# Smart-LCD_1V1.net
KiCad netlist of a schematic drawn in EAGLE
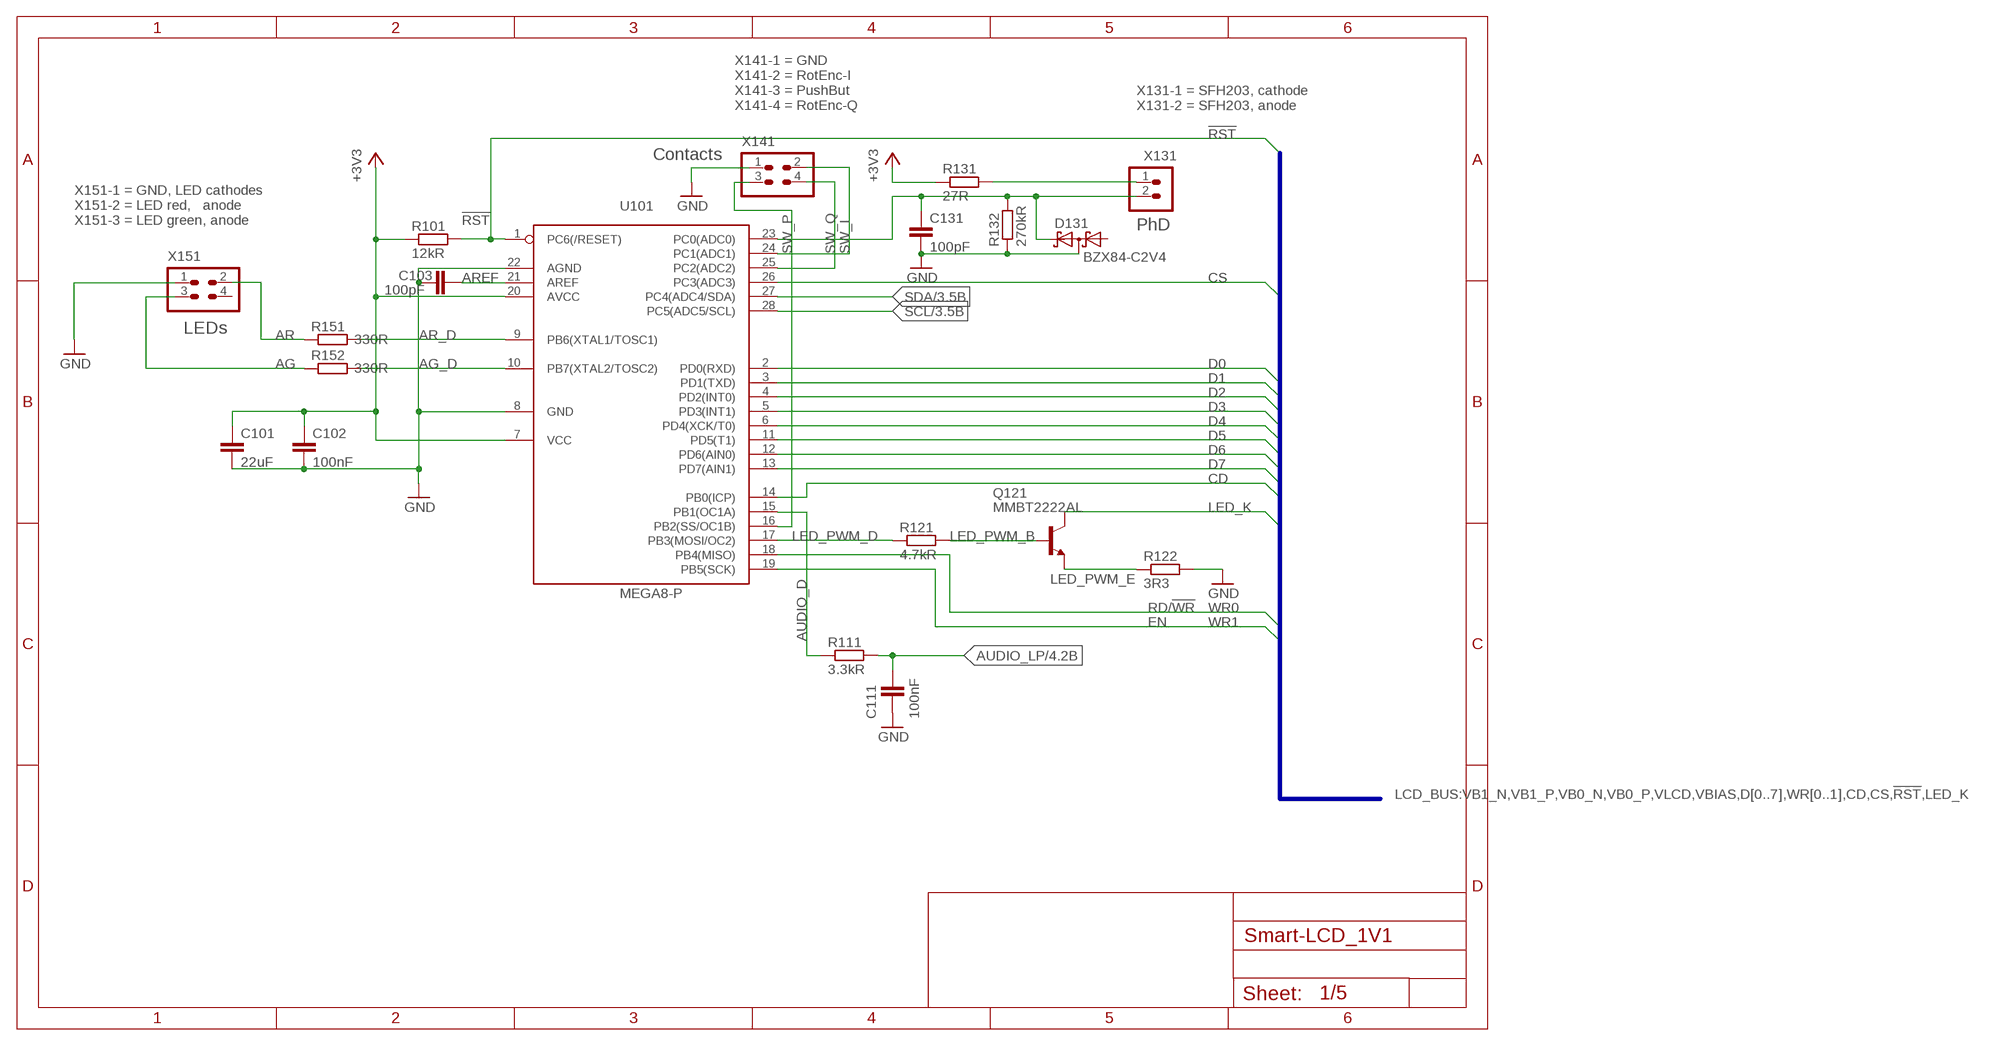
[diagram p0: schematic, sheet 1]
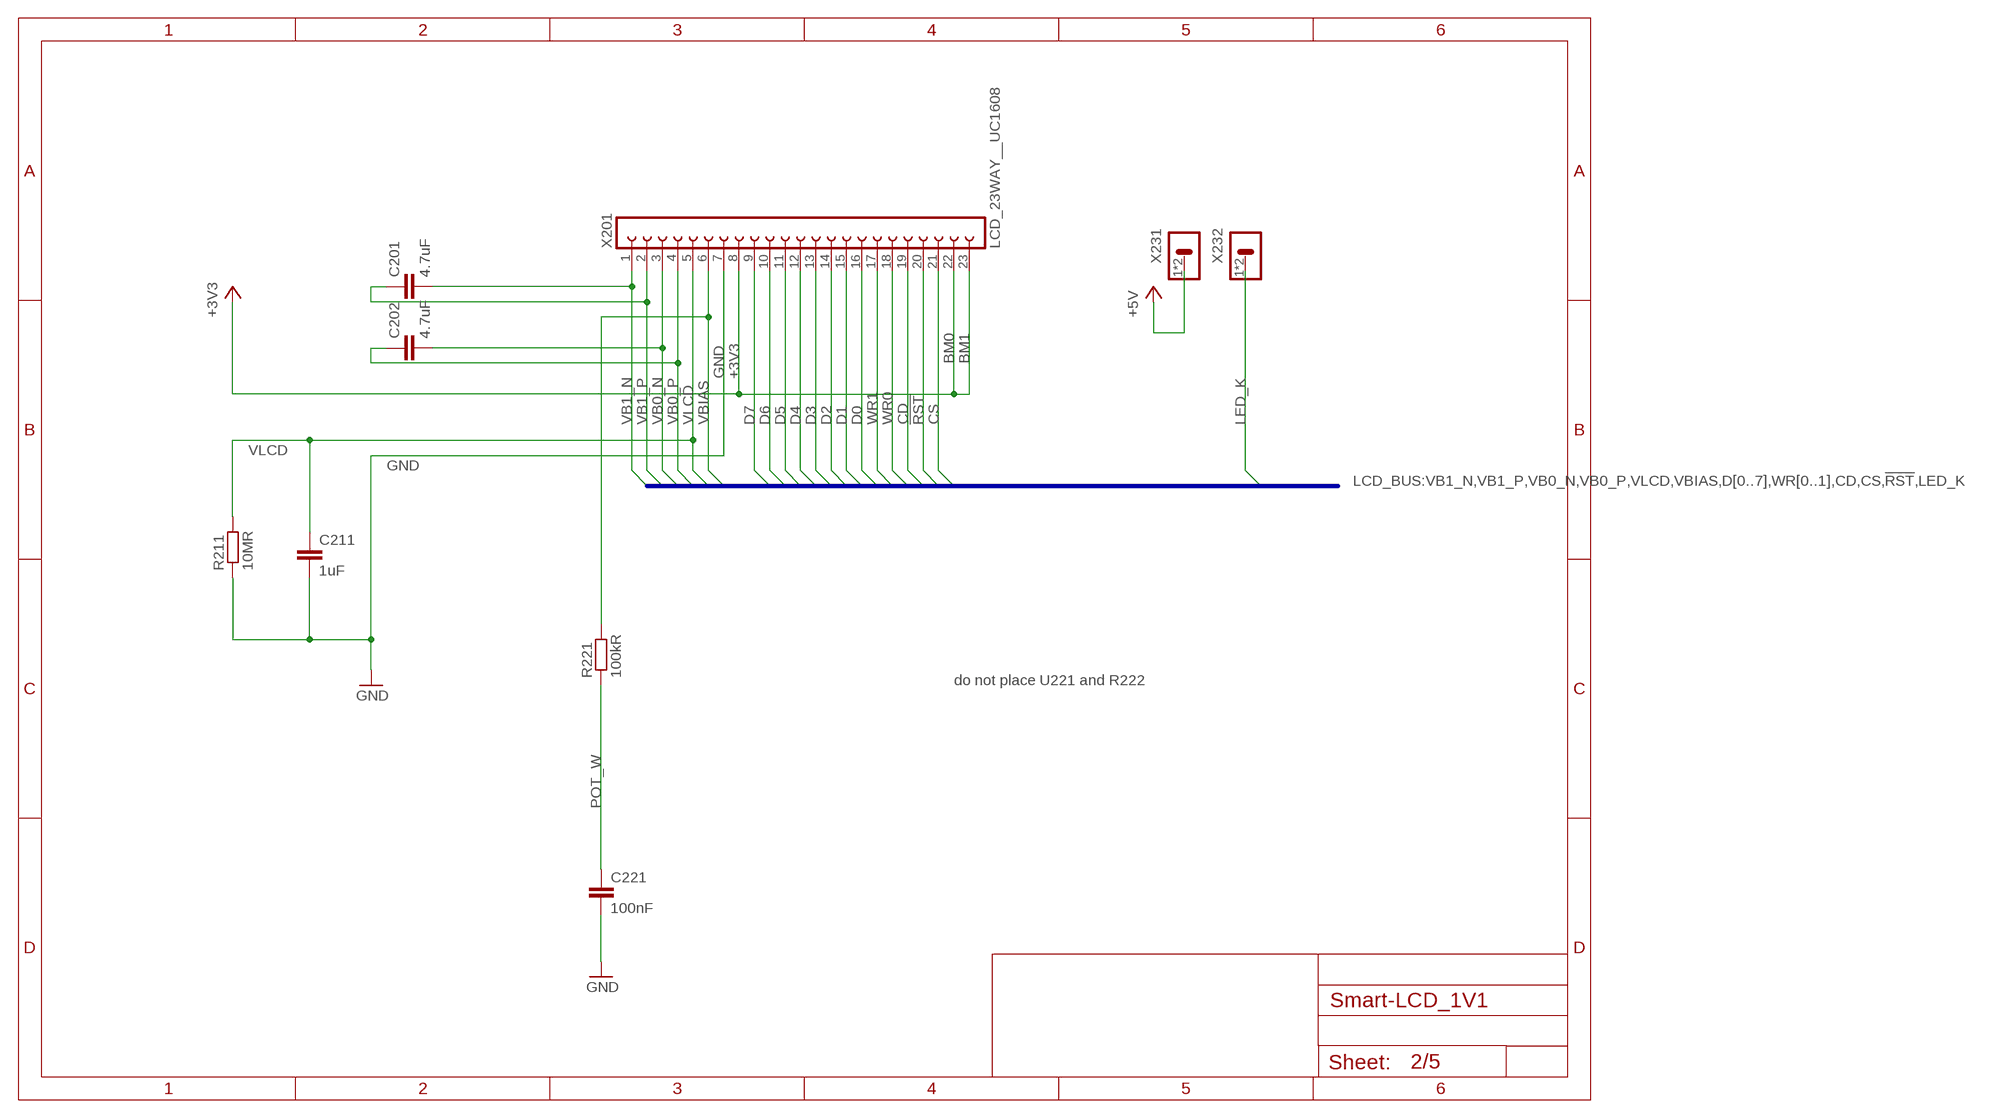
[diagram p1: schematic, sheet 2]
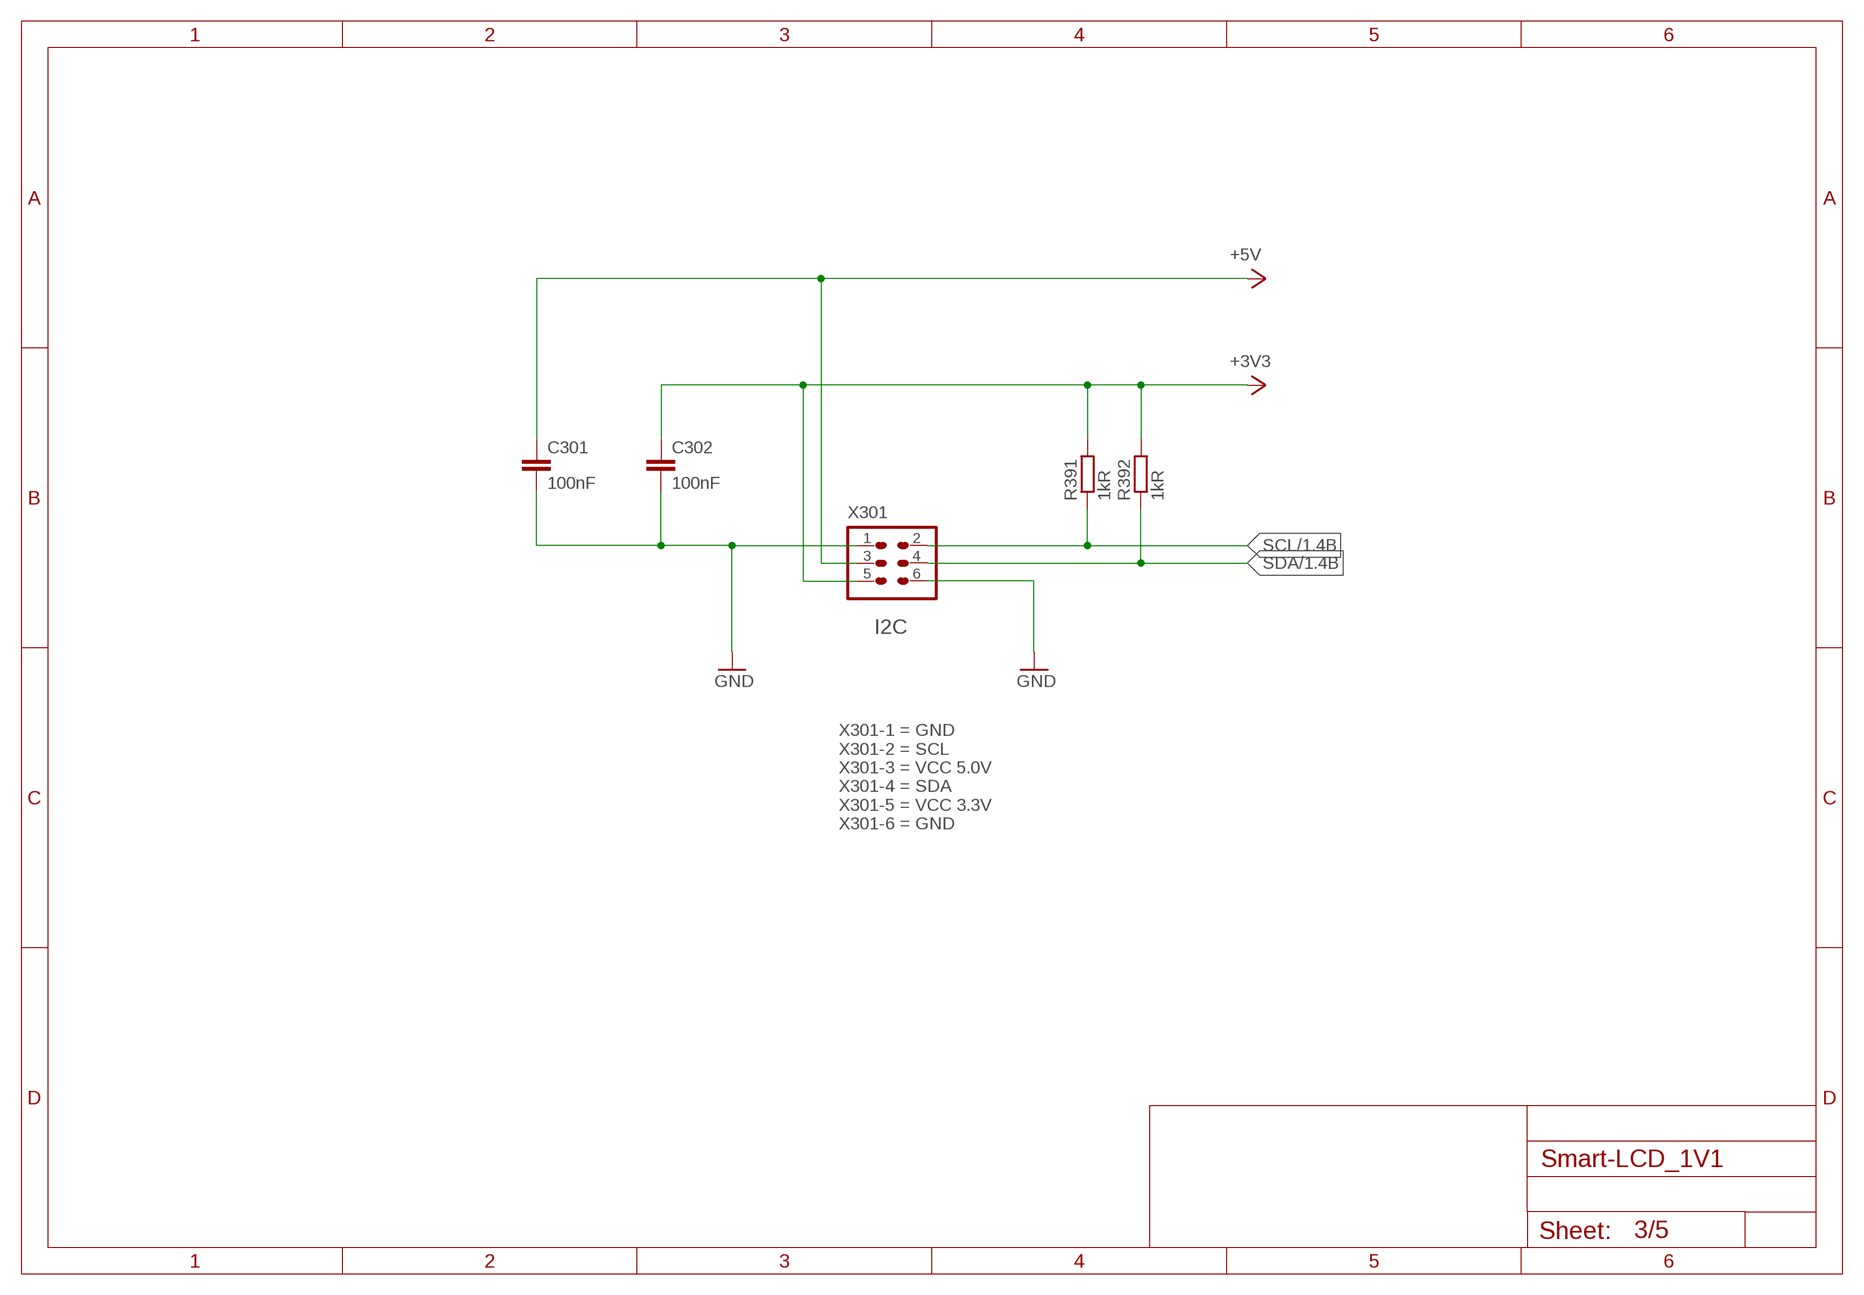
[diagram p2: schematic, sheet 3]
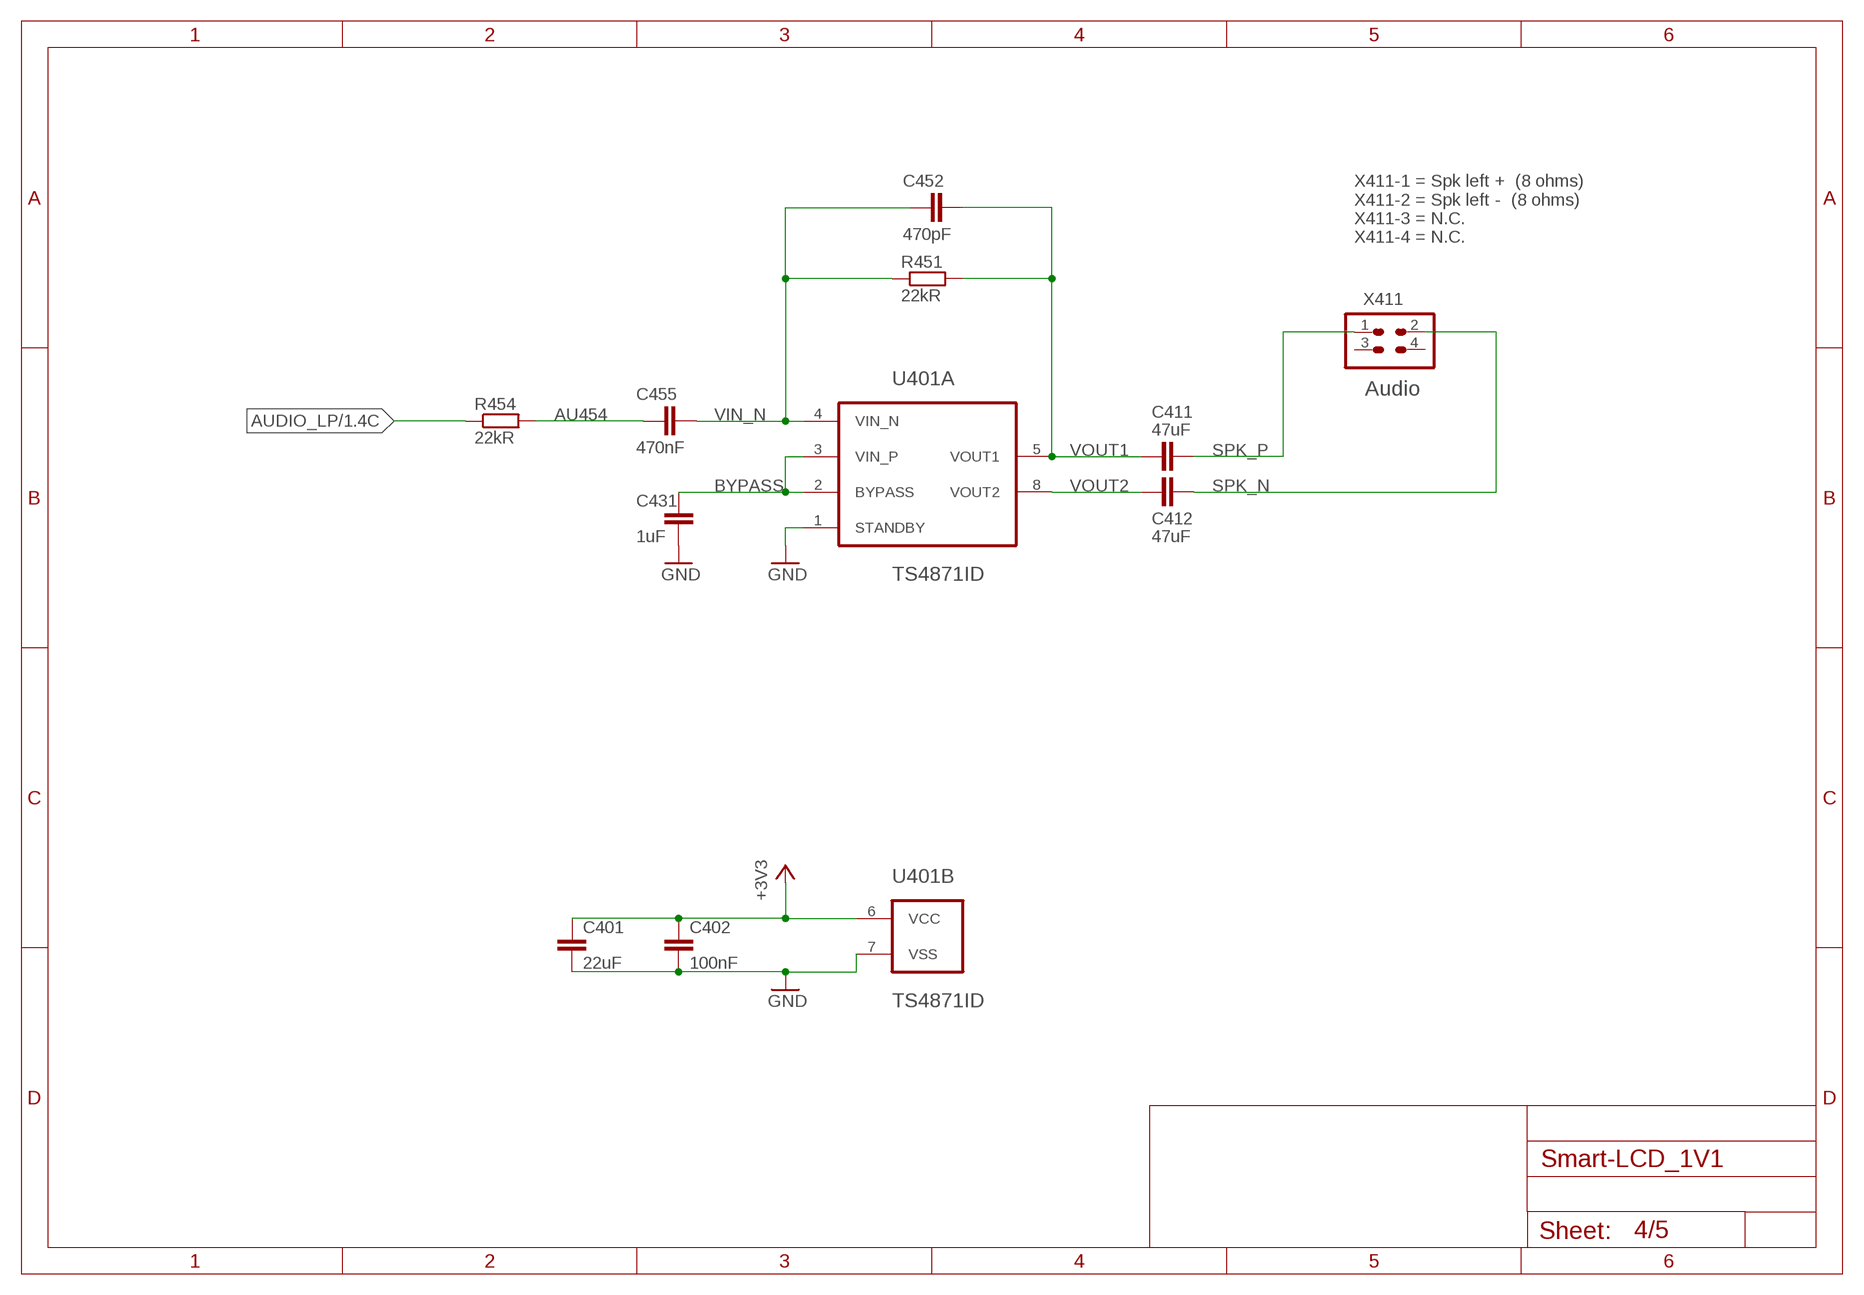
[diagram p3: schematic, sheet 4]
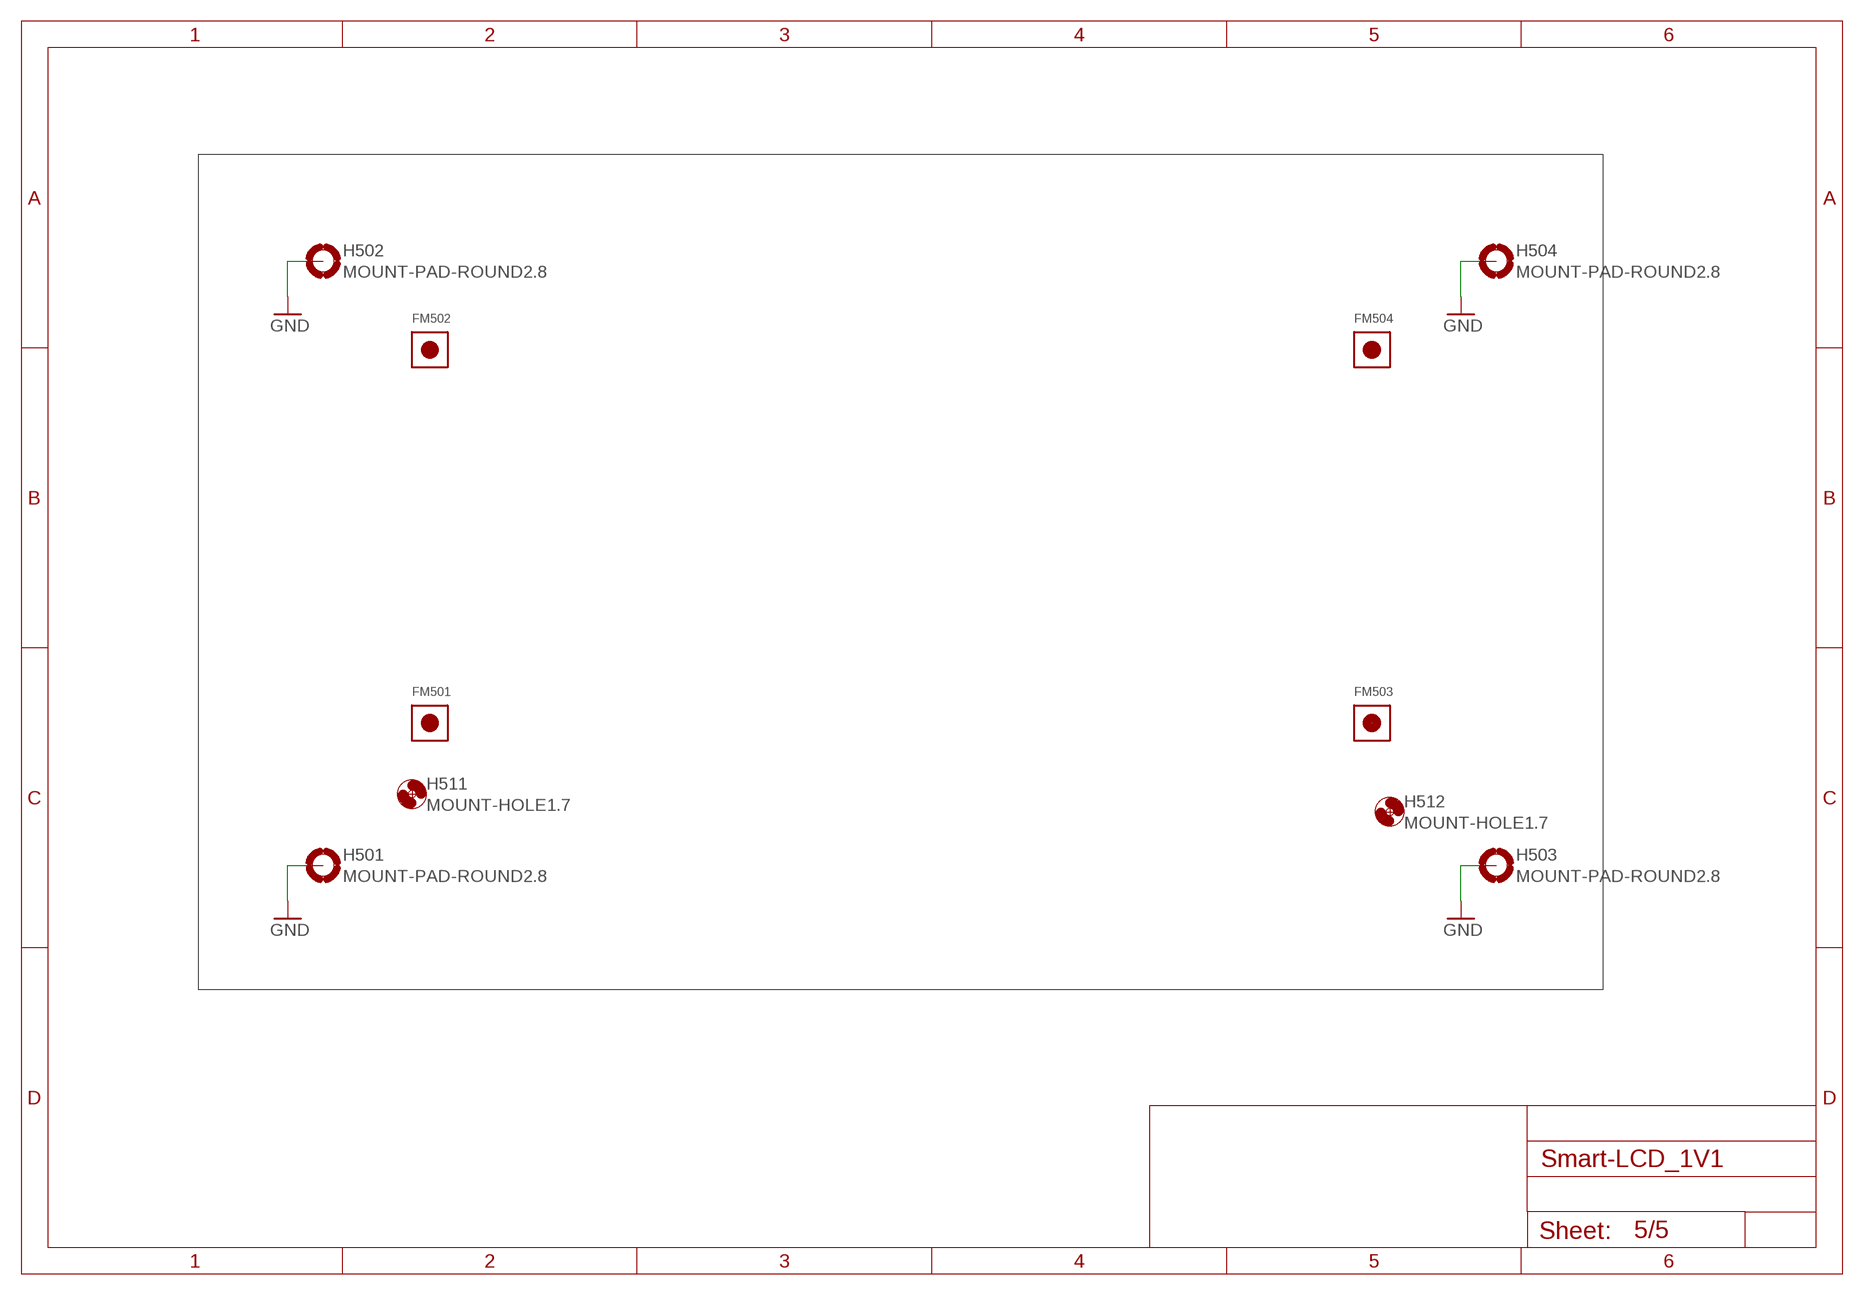
[diagram p4: schematic, sheet 5]

(export (version "E")
  (design (tool "Eeschema 10.0.6"))
  (components
    (comp (ref "C201")
      (value "4.7uF")
      (footprint "eagle-import:C0805")
      (libsource (lib "eagle-import") (part "C-EUC0805"))
    )
    (comp (ref "C202")
      (value "4.7uF")
      (footprint "eagle-import:C0805")
      (libsource (lib "eagle-import") (part "C-EUC0805"))
    )
    (comp (ref "C211")
      (value "1uF")
      (footprint "eagle-import:C0805")
      (libsource (lib "eagle-import") (part "C-EUC0805"))
    )
    (comp (ref "C221")
      (value "100nF")
      (footprint "eagle-import:C0805")
      (libsource (lib "eagle-import") (part "C-EUC0805"))
    )
    (comp (ref "R211")
      (value "10MR")
      (footprint "eagle-import:R0805")
      (libsource (lib "eagle-import") (part "R-EU_R0805"))
    )
    (comp (ref "R221")
      (value "100kR")
      (footprint "eagle-import:R0805")
      (libsource (lib "eagle-import") (part "R-EU_R0805"))
    )
    (comp (ref "X201")
      (value "LCD_23WAY__UC1608")
      (footprint "eagle-import:23X01_1MM27__UC1608")
      (libsource (lib "eagle-import") (part "LCD_23WAY__UC1608"))
    )
    (comp (ref "X231")
      (value "LED_A")
      (footprint "eagle-import:P1-20X0.80")
      (libsource (lib "eagle-import") (part "CON_1X"))
    )
    (comp (ref "X232")
      (value "LED_K")
      (footprint "eagle-import:P1-20X0.80")
      (libsource (lib "eagle-import") (part "CON_1X"))
    )
    (comp (ref "C101")
      (value "22uF")
      (footprint "eagle-import:C0805")
      (libsource (lib "eagle-import") (part "C-EUC0805"))
    )
    (comp (ref "C102")
      (value "100nF")
      (footprint "eagle-import:C0805")
      (libsource (lib "eagle-import") (part "C-EUC0805"))
    )
    (comp (ref "C103")
      (value "100pF")
      (footprint "eagle-import:C0805")
      (libsource (lib "eagle-import") (part "C-EUC0805"))
    )
    (comp (ref "C111")
      (value "100nF")
      (footprint "eagle-import:C0805")
      (libsource (lib "eagle-import") (part "C-EUC0805"))
    )
    (comp (ref "C131")
      (value "100pF")
      (footprint "eagle-import:C0805")
      (libsource (lib "eagle-import") (part "C-EUC0805"))
    )
    (comp (ref "D131")
      (value "BZX84-C2V4")
      (footprint "eagle-import:SOT23")
      (libsource (lib "eagle-import") (part "BAS70-04"))
    )
    (comp (ref "Q121")
      (value "MMBT2222AL")
      (footprint "eagle-import:SOT23")
      (libsource (lib "eagle-import") (part "MMBT2222AL"))
    )
    (comp (ref "R101")
      (value "12kR")
      (footprint "eagle-import:R0805")
      (libsource (lib "eagle-import") (part "R-EU_R0805"))
    )
    (comp (ref "R111")
      (value "3.3kR")
      (footprint "eagle-import:R0805")
      (libsource (lib "eagle-import") (part "R-EU_R0805"))
    )
    (comp (ref "R121")
      (value "4.7kR")
      (footprint "eagle-import:R0805")
      (libsource (lib "eagle-import") (part "R-EU_R0805"))
    )
    (comp (ref "R122")
      (value "3R3")
      (footprint "eagle-import:R0805")
      (libsource (lib "eagle-import") (part "R-EU_R0805"))
    )
    (comp (ref "R131")
      (value "27R")
      (footprint "eagle-import:R0805")
      (libsource (lib "eagle-import") (part "R-EU_R0805"))
    )
    (comp (ref "R132")
      (value "270kR")
      (footprint "eagle-import:R0805")
      (libsource (lib "eagle-import") (part "R-EU_R0805"))
    )
    (comp (ref "R151")
      (value "330R")
      (footprint "eagle-import:R0805")
      (libsource (lib "eagle-import") (part "R-EU_R0805"))
    )
    (comp (ref "R152")
      (value "330R")
      (footprint "eagle-import:R0805")
      (libsource (lib "eagle-import") (part "R-EU_R0805"))
    )
    (comp (ref "U101")
      (value "MEGA8-P")
      (footprint "eagle-import:DIL28-3")
      (libsource (lib "eagle-import") (part "MEGA8-P"))
    )
    (comp (ref "X131")
      (value "LDR")
      (footprint "eagle-import:1X02")
      (libsource (lib "eagle-import") (part "HEADER-1X2"))
    )
    (comp (ref "X141")
      (value "Switches")
      (footprint "eagle-import:2X02")
      (libsource (lib "eagle-import") (part "HEADER-2X2"))
    )
    (comp (ref "X151")
      (value "LEDs")
      (footprint "eagle-import:2X02")
      (libsource (lib "eagle-import") (part "HEADER-2X2"))
    )
    (comp (ref "FM501")
      (value "FIDUCIAL_MARK_1MM")
      (footprint "eagle-import:FIDUCIAL_MARK_1MM")
      (libsource (lib "eagle-import") (part "FIDUCIAL_MARK_1MM"))
    )
    (comp (ref "FM502")
      (value "FIDUCIAL_MARK_1MM")
      (footprint "eagle-import:FIDUCIAL_MARK_1MM")
      (libsource (lib "eagle-import") (part "FIDUCIAL_MARK_1MM"))
    )
    (comp (ref "FM503")
      (value "FIDUCIAL_MARK_1MM")
      (footprint "eagle-import:FIDUCIAL_MARK_1MM")
      (libsource (lib "eagle-import") (part "FIDUCIAL_MARK_1MM"))
    )
    (comp (ref "FM504")
      (value "FIDUCIAL_MARK_1MM")
      (footprint "eagle-import:FIDUCIAL_MARK_1MM")
      (libsource (lib "eagle-import") (part "FIDUCIAL_MARK_1MM"))
    )
    (comp (ref "H501")
      (value "MOUNT-PAD-ROUND2.8")
      (footprint "eagle-import:2,8-PAD")
      (libsource (lib "eagle-import") (part "MOUNT-PAD-ROUND2.8"))
    )
    (comp (ref "H502")
      (value "MOUNT-PAD-ROUND2.8")
      (footprint "eagle-import:2,8-PAD")
      (libsource (lib "eagle-import") (part "MOUNT-PAD-ROUND2.8"))
    )
    (comp (ref "H503")
      (value "MOUNT-PAD-ROUND2.8")
      (footprint "eagle-import:2,8-PAD")
      (libsource (lib "eagle-import") (part "MOUNT-PAD-ROUND2.8"))
    )
    (comp (ref "H504")
      (value "MOUNT-PAD-ROUND2.8")
      (footprint "eagle-import:2,8-PAD")
      (libsource (lib "eagle-import") (part "MOUNT-PAD-ROUND2.8"))
    )
    (comp (ref "H511")
      (value "MOUNT-HOLE1.7")
      (footprint "eagle-import:1,7")
      (libsource (lib "eagle-import") (part "MOUNT-HOLE1.7"))
    )
    (comp (ref "H512")
      (value "MOUNT-HOLE1.7")
      (footprint "eagle-import:1,7")
      (libsource (lib "eagle-import") (part "MOUNT-HOLE1.7"))
    )
    (comp (ref "C301")
      (value "100nF")
      (footprint "eagle-import:C0805")
      (libsource (lib "eagle-import") (part "C-EUC0805"))
    )
    (comp (ref "C302")
      (value "100nF")
      (footprint "eagle-import:C0805")
      (libsource (lib "eagle-import") (part "C-EUC0805"))
    )
    (comp (ref "R391")
      (value "1kR")
      (footprint "eagle-import:R0805")
      (libsource (lib "eagle-import") (part "R-EU_R0805"))
    )
    (comp (ref "R392")
      (value "1kR")
      (footprint "eagle-import:R0805")
      (libsource (lib "eagle-import") (part "R-EU_R0805"))
    )
    (comp (ref "X301")
      (value "I2C")
      (footprint "eagle-import:2X03")
      (libsource (lib "eagle-import") (part "HEADER-2X3"))
    )
    (comp (ref "C401")
      (value "22uF")
      (footprint "eagle-import:C0805")
      (libsource (lib "eagle-import") (part "C-EUC0805"))
    )
    (comp (ref "C402")
      (value "100nF")
      (footprint "eagle-import:C0805")
      (libsource (lib "eagle-import") (part "C-EUC0805"))
    )
    (comp (ref "C411")
      (value "47uF")
      (footprint "eagle-import:C0805")
      (libsource (lib "eagle-import") (part "C-EUC0805"))
    )
    (comp (ref "C412")
      (value "47uF")
      (footprint "eagle-import:C0805")
      (libsource (lib "eagle-import") (part "C-EUC0805"))
    )
    (comp (ref "C431")
      (value "1uF")
      (footprint "eagle-import:C0805")
      (libsource (lib "eagle-import") (part "C-EUC0805"))
    )
    (comp (ref "C452")
      (value "470pF")
      (footprint "eagle-import:C0805")
      (libsource (lib "eagle-import") (part "C-EUC0805"))
    )
    (comp (ref "C455")
      (value "470nF")
      (footprint "eagle-import:C0805")
      (libsource (lib "eagle-import") (part "C-EUC0805"))
    )
    (comp (ref "R451")
      (value "22kR")
      (footprint "eagle-import:R0805")
      (libsource (lib "eagle-import") (part "R-EU_R0805"))
    )
    (comp (ref "R454")
      (value "22kR")
      (footprint "eagle-import:R0805")
      (libsource (lib "eagle-import") (part "R-EU_R0805"))
    )
    (comp (ref "U401")
      (value "TS4871ID")
      (footprint "eagle-import:SO08")
      (libsource (lib "eagle-import") (part "TS4871ID"))
    )
    (comp (ref "X411")
      (value "Audio")
      (footprint "eagle-import:2X02")
      (libsource (lib "eagle-import") (part "HEADER-2X2"))
    )
  )
  (nets
    (net (code "8") (name "+3V3") (class "Default")
      (node (ref "C101") (pin "1") (pinfunction "1_1") (pintype "passive"))
      (node (ref "C102") (pin "1") (pinfunction "1_1") (pintype "passive"))
      (node (ref "C302") (pin "1") (pinfunction "1_1") (pintype "passive"))
      (node (ref "C401") (pin "1") (pinfunction "1_1") (pintype "passive"))
      (node (ref "C402") (pin "1") (pinfunction "1_1") (pintype "passive"))
      (node (ref "R101") (pin "1") (pinfunction "1_1") (pintype "passive"))
      (node (ref "R131") (pin "1") (pinfunction "1_1") (pintype "passive"))
      (node (ref "R391") (pin "2") (pinfunction "2_2") (pintype "passive"))
      (node (ref "R392") (pin "2") (pinfunction "2_2") (pintype "passive"))
      (node (ref "U101") (pin "20") (pinfunction "AVCC_20") (pintype "bidirectional"))
      (node (ref "U101") (pin "7") (pinfunction "VCC_7") (pintype "bidirectional"))
      (node (ref "U401") (pin "6") (pinfunction "VCC_6") (pintype "power_in"))
      (node (ref "X201") (pin "22") (pinfunction "22_22") (pintype "passive"))
      (node (ref "X201") (pin "23") (pinfunction "23_23") (pintype "passive"))
      (node (ref "X201") (pin "8") (pinfunction "8_8") (pintype "passive"))
      (node (ref "X301") (pin "5") (pinfunction "5_5") (pintype "passive"))
    )
    (net (code "9") (name "+5V") (class "Default")
      (node (ref "C301") (pin "1") (pinfunction "1_1") (pintype "passive"))
      (node (ref "X231") (pin "1") (pinfunction "1_1") (pintype "passive"))
      (node (ref "X231") (pin "2") (pinfunction "1_2") (pintype "passive"))
      (node (ref "X301") (pin "3") (pinfunction "3_3") (pintype "passive"))
    )
    (net (code "12") (name "AG") (class "Default")
      (node (ref "R152") (pin "1") (pinfunction "1_1") (pintype "passive"))
      (node (ref "X151") (pin "3") (pinfunction "3_3") (pintype "passive"))
    )
    (net (code "13") (name "AG_D") (class "Default")
      (node (ref "R152") (pin "2") (pinfunction "2_2") (pintype "passive"))
      (node (ref "U101") (pin "10") (pinfunction "PB7(XTAL2/TOSC2)_10") (pintype "bidirectional"))
    )
    (net (code "14") (name "AR") (class "Default")
      (node (ref "R151") (pin "1") (pinfunction "1_1") (pintype "passive"))
      (node (ref "X151") (pin "2") (pinfunction "2_2") (pintype "passive"))
    )
    (net (code "15") (name "AREF") (class "Default")
      (node (ref "C103") (pin "2") (pinfunction "2_2") (pintype "passive"))
      (node (ref "U101") (pin "21") (pinfunction "AREF_21") (pintype "bidirectional"))
    )
    (net (code "16") (name "AR_D") (class "Default")
      (node (ref "R151") (pin "2") (pinfunction "2_2") (pintype "passive"))
      (node (ref "U101") (pin "9") (pinfunction "PB6(XTAL1/TOSC1)_9") (pintype "bidirectional"))
    )
    (net (code "17") (name "AU454") (class "Default")
      (node (ref "C455") (pin "1") (pinfunction "1_1") (pintype "passive"))
      (node (ref "R454") (pin "2") (pinfunction "2_2") (pintype "passive"))
    )
    (net (code "18") (name "AUDIO_D") (class "Default")
      (node (ref "R111") (pin "1") (pinfunction "1_1") (pintype "passive"))
      (node (ref "U101") (pin "15") (pinfunction "PB1(OC1A)_15") (pintype "bidirectional"))
    )
    (net (code "19") (name "AUDIO_LP") (class "Default")
      (node (ref "C111") (pin "1") (pinfunction "1_1") (pintype "passive"))
      (node (ref "R111") (pin "2") (pinfunction "2_2") (pintype "passive"))
      (node (ref "R454") (pin "1") (pinfunction "1_1") (pintype "passive"))
    )
    (net (code "20") (name "BYPASS") (class "Default")
      (node (ref "C431") (pin "1") (pinfunction "1_1") (pintype "passive"))
      (node (ref "U401") (pin "2") (pinfunction "BYPASS_2") (pintype "passive"))
      (node (ref "U401") (pin "3") (pinfunction "VIN_P_3") (pintype "passive"))
    )
    (net (code "21") (name "CD") (class "Default")
      (node (ref "U101") (pin "14") (pinfunction "PB0(ICP)_14") (pintype "bidirectional"))
      (node (ref "X201") (pin "19") (pinfunction "19_19") (pintype "passive"))
    )
    (net (code "22") (name "CS") (class "Default")
      (node (ref "U101") (pin "26") (pinfunction "PC3(ADC3)_26") (pintype "bidirectional"))
      (node (ref "X201") (pin "21") (pinfunction "21_21") (pintype "passive"))
    )
    (net (code "23") (name "D0") (class "Default")
      (node (ref "U101") (pin "2") (pinfunction "PD0(RXD)_2") (pintype "bidirectional"))
      (node (ref "X201") (pin "16") (pinfunction "16_16") (pintype "passive"))
    )
    (net (code "24") (name "D1") (class "Default")
      (node (ref "U101") (pin "3") (pinfunction "PD1(TXD)_3") (pintype "bidirectional"))
      (node (ref "X201") (pin "15") (pinfunction "15_15") (pintype "passive"))
    )
    (net (code "25") (name "D2") (class "Default")
      (node (ref "U101") (pin "4") (pinfunction "PD2(INT0)_4") (pintype "bidirectional"))
      (node (ref "X201") (pin "14") (pinfunction "14_14") (pintype "passive"))
    )
    (net (code "26") (name "D3") (class "Default")
      (node (ref "U101") (pin "5") (pinfunction "PD3(INT1)_5") (pintype "bidirectional"))
      (node (ref "X201") (pin "13") (pinfunction "13_13") (pintype "passive"))
    )
    (net (code "27") (name "D4") (class "Default")
      (node (ref "U101") (pin "6") (pinfunction "PD4(XCK/T0)_6") (pintype "bidirectional"))
      (node (ref "X201") (pin "12") (pinfunction "12_12") (pintype "passive"))
    )
    (net (code "28") (name "D5") (class "Default")
      (node (ref "U101") (pin "11") (pinfunction "PD5(T1)_11") (pintype "bidirectional"))
      (node (ref "X201") (pin "11") (pinfunction "11_11") (pintype "passive"))
    )
    (net (code "29") (name "D6") (class "Default")
      (node (ref "U101") (pin "12") (pinfunction "PD6(AIN0)_12") (pintype "bidirectional"))
      (node (ref "X201") (pin "10") (pinfunction "10_10") (pintype "passive"))
    )
    (net (code "30") (name "D7") (class "Default")
      (node (ref "U101") (pin "13") (pinfunction "PD7(AIN1)_13") (pintype "bidirectional"))
      (node (ref "X201") (pin "9") (pinfunction "9_9") (pintype "passive"))
    )
    (net (code "31") (name "GND") (class "Default")
      (node (ref "C101") (pin "2") (pinfunction "2_2") (pintype "passive"))
      (node (ref "C102") (pin "2") (pinfunction "2_2") (pintype "passive"))
      (node (ref "C103") (pin "1") (pinfunction "1_1") (pintype "passive"))
      (node (ref "C111") (pin "2") (pinfunction "2_2") (pintype "passive"))
      (node (ref "C131") (pin "2") (pinfunction "2_2") (pintype "passive"))
      (node (ref "C211") (pin "2") (pinfunction "2_2") (pintype "passive"))
      (node (ref "C221") (pin "2") (pinfunction "2_2") (pintype "passive"))
      (node (ref "C301") (pin "2") (pinfunction "2_2") (pintype "passive"))
      (node (ref "C302") (pin "2") (pinfunction "2_2") (pintype "passive"))
      (node (ref "C401") (pin "2") (pinfunction "2_2") (pintype "passive"))
      (node (ref "C402") (pin "2") (pinfunction "2_2") (pintype "passive"))
      (node (ref "C431") (pin "2") (pinfunction "2_2") (pintype "passive"))
      (node (ref "D131") (pin "3") (pinfunction "C1A2_3") (pintype "passive"))
      (node (ref "H501") (pin "B2,8") (pinfunction "MOUNT_B2,8") (pintype "passive"))
      (node (ref "H502") (pin "B2,8") (pinfunction "MOUNT_B2,8") (pintype "passive"))
      (node (ref "H503") (pin "B2,8") (pinfunction "MOUNT_B2,8") (pintype "passive"))
      (node (ref "H504") (pin "B2,8") (pinfunction "MOUNT_B2,8") (pintype "passive"))
      (node (ref "R122") (pin "2") (pinfunction "2_2") (pintype "passive"))
      (node (ref "R132") (pin "1") (pinfunction "1_1") (pintype "passive"))
      (node (ref "R211") (pin "1") (pinfunction "1_1") (pintype "passive"))
      (node (ref "U101") (pin "22") (pinfunction "AGND_22") (pintype "bidirectional"))
      (node (ref "U101") (pin "8") (pinfunction "GND_8") (pintype "bidirectional"))
      (node (ref "U401") (pin "1") (pinfunction "STANDBY_1") (pintype "input"))
      (node (ref "U401") (pin "7") (pinfunction "VSS_7") (pintype "power_in"))
      (node (ref "X141") (pin "1") (pinfunction "1_1") (pintype "passive"))
      (node (ref "X151") (pin "1") (pinfunction "1_1") (pintype "passive"))
      (node (ref "X201") (pin "7") (pinfunction "7_7") (pintype "passive"))
      (node (ref "X301") (pin "1") (pinfunction "1_1") (pintype "passive"))
      (node (ref "X301") (pin "6") (pinfunction "6_6") (pintype "passive"))
    )
    (net (code "32") (name "LED_K") (class "Default")
      (node (ref "Q121") (pin "3") (pinfunction "C_3") (pintype "passive"))
      (node (ref "X232") (pin "1") (pinfunction "1_1") (pintype "passive"))
      (node (ref "X232") (pin "2") (pinfunction "1_2") (pintype "passive"))
    )
    (net (code "33") (name "LED_PWM_B") (class "Default")
      (node (ref "Q121") (pin "1") (pinfunction "B_1") (pintype "passive"))
      (node (ref "R121") (pin "2") (pinfunction "2_2") (pintype "passive"))
    )
    (net (code "34") (name "LED_PWM_D") (class "Default")
      (node (ref "R121") (pin "1") (pinfunction "1_1") (pintype "passive"))
      (node (ref "U101") (pin "17") (pinfunction "PB3(MOSI/OC2)_17") (pintype "bidirectional"))
    )
    (net (code "35") (name "LED_PWM_E") (class "Default")
      (node (ref "Q121") (pin "2") (pinfunction "E_2") (pintype "passive"))
      (node (ref "R122") (pin "1") (pinfunction "1_1") (pintype "passive"))
    )
    (net (code "36") (name "Net-(D131-C2)") (class "Default")
      (node (ref "C131") (pin "1") (pinfunction "1_1") (pintype "passive"))
      (node (ref "D131") (pin "2") (pinfunction "C2_2") (pintype "passive"))
      (node (ref "R132") (pin "2") (pinfunction "2_2") (pintype "passive"))
      (node (ref "U101") (pin "23") (pinfunction "PC0(ADC0)_23") (pintype "bidirectional"))
      (node (ref "X131") (pin "2") (pinfunction "2_2") (pintype "passive"))
    )
    (net (code "37") (name "Net-(R131-Pad2)") (class "Default")
      (node (ref "R131") (pin "2") (pinfunction "2_2") (pintype "passive"))
      (node (ref "X131") (pin "1") (pinfunction "1_1") (pintype "passive"))
    )
    (net (code "38") (name "POT_W") (class "Default")
      (node (ref "C221") (pin "1") (pinfunction "1_1") (pintype "passive"))
      (node (ref "R221") (pin "1") (pinfunction "1_1") (pintype "passive"))
    )
    (net (code "39") (name "SCL") (class "Default")
      (node (ref "R391") (pin "1") (pinfunction "1_1") (pintype "passive"))
      (node (ref "U101") (pin "28") (pinfunction "PC5(ADC5/SCL)_28") (pintype "bidirectional"))
      (node (ref "X301") (pin "2") (pinfunction "2_2") (pintype "passive"))
    )
    (net (code "40") (name "SDA") (class "Default")
      (node (ref "R392") (pin "1") (pinfunction "1_1") (pintype "passive"))
      (node (ref "U101") (pin "27") (pinfunction "PC4(ADC4/SDA)_27") (pintype "bidirectional"))
      (node (ref "X301") (pin "4") (pinfunction "4_4") (pintype "passive"))
    )
    (net (code "41") (name "SPK_N") (class "Default")
      (node (ref "C412") (pin "2") (pinfunction "2_2") (pintype "passive"))
      (node (ref "X411") (pin "2") (pinfunction "2_2") (pintype "passive"))
    )
    (net (code "42") (name "SPK_P") (class "Default")
      (node (ref "C411") (pin "2") (pinfunction "2_2") (pintype "passive"))
      (node (ref "X411") (pin "1") (pinfunction "1_1") (pintype "passive"))
    )
    (net (code "43") (name "SW_I") (class "Default")
      (node (ref "U101") (pin "24") (pinfunction "PC1(ADC1)_24") (pintype "bidirectional"))
      (node (ref "X141") (pin "2") (pinfunction "2_2") (pintype "passive"))
    )
    (net (code "44") (name "SW_P") (class "Default")
      (node (ref "U101") (pin "16") (pinfunction "PB2(SS/OC1B)_16") (pintype "bidirectional"))
      (node (ref "X141") (pin "3") (pinfunction "3_3") (pintype "passive"))
    )
    (net (code "45") (name "SW_Q") (class "Default")
      (node (ref "U101") (pin "25") (pinfunction "PC2(ADC2)_25") (pintype "bidirectional"))
      (node (ref "X141") (pin "4") (pinfunction "4_4") (pintype "passive"))
    )
    (net (code "46") (name "VB0_N") (class "Default")
      (node (ref "C202") (pin "2") (pinfunction "2_2") (pintype "passive"))
      (node (ref "X201") (pin "3") (pinfunction "3_3") (pintype "passive"))
    )
    (net (code "47") (name "VB0_P") (class "Default")
      (node (ref "C202") (pin "1") (pinfunction "1_1") (pintype "passive"))
      (node (ref "X201") (pin "4") (pinfunction "4_4") (pintype "passive"))
    )
    (net (code "48") (name "VB1_N") (class "Default")
      (node (ref "C201") (pin "2") (pinfunction "2_2") (pintype "passive"))
      (node (ref "X201") (pin "1") (pinfunction "1_1") (pintype "passive"))
    )
    (net (code "49") (name "VB1_P") (class "Default")
      (node (ref "C201") (pin "1") (pinfunction "1_1") (pintype "passive"))
      (node (ref "X201") (pin "2") (pinfunction "2_2") (pintype "passive"))
    )
    (net (code "50") (name "VBIAS") (class "Default")
      (node (ref "R221") (pin "2") (pinfunction "2_2") (pintype "passive"))
      (node (ref "X201") (pin "6") (pinfunction "6_6") (pintype "passive"))
    )
    (net (code "51") (name "VIN_N") (class "Default")
      (node (ref "C452") (pin "1") (pinfunction "1_1") (pintype "passive"))
      (node (ref "C455") (pin "2") (pinfunction "2_2") (pintype "passive"))
      (node (ref "R451") (pin "1") (pinfunction "1_1") (pintype "passive"))
      (node (ref "U401") (pin "4") (pinfunction "VIN_N_4") (pintype "passive"))
    )
    (net (code "52") (name "VLCD") (class "Default")
      (node (ref "C211") (pin "1") (pinfunction "1_1") (pintype "passive"))
      (node (ref "R211") (pin "2") (pinfunction "2_2") (pintype "passive"))
      (node (ref "X201") (pin "5") (pinfunction "5_5") (pintype "passive"))
    )
    (net (code "53") (name "VOUT1") (class "Default")
      (node (ref "C411") (pin "1") (pinfunction "1_1") (pintype "passive"))
      (node (ref "C452") (pin "2") (pinfunction "2_2") (pintype "passive"))
      (node (ref "R451") (pin "2") (pinfunction "2_2") (pintype "passive"))
      (node (ref "U401") (pin "5") (pinfunction "VOUT1_5") (pintype "passive"))
    )
    (net (code "54") (name "VOUT2") (class "Default")
      (node (ref "C412") (pin "1") (pinfunction "1_1") (pintype "passive"))
      (node (ref "U401") (pin "8") (pinfunction "VOUT2_8") (pintype "passive"))
    )
    (net (code "55") (name "WR0") (class "Default")
      (node (ref "U101") (pin "18") (pinfunction "PB4(MISO)_18") (pintype "bidirectional"))
      (node (ref "X201") (pin "18") (pinfunction "18_18") (pintype "passive"))
    )
    (net (code "56") (name "WR1") (class "Default")
      (node (ref "U101") (pin "19") (pinfunction "PB5(SCK)_19") (pintype "bidirectional"))
      (node (ref "X201") (pin "17") (pinfunction "17_17") (pintype "passive"))
    )
    (net (code "57") (name "unconnected-(D131-A1-Pad1)") (class "Default")
      (node (ref "D131") (pin "1") (pinfunction "A1_1") (pintype "passive"))
    )
    (net (code "58") (name "unconnected-(X151-Pad4)") (class "Default")
      (node (ref "X151") (pin "4") (pinfunction "4_4") (pintype "passive"))
    )
    (net (code "59") (name "unconnected-(X411-Pad3)") (class "Default")
      (node (ref "X411") (pin "3") (pinfunction "3_3") (pintype "passive"))
    )
    (net (code "60") (name "unconnected-(X411-Pad4)") (class "Default")
      (node (ref "X411") (pin "4") (pinfunction "4_4") (pintype "passive"))
    )
    (net (code "61") (name "~{RST}") (class "Default")
      (node (ref "R101") (pin "2") (pinfunction "2_2") (pintype "passive"))
      (node (ref "U101") (pin "1") (pinfunction "PC6(/RESET)_1") (pintype "bidirectional"))
      (node (ref "X201") (pin "20") (pinfunction "20_20") (pintype "passive"))
    )
  )
)
